# Sheet_1_2021-07-19.net
KiCad netlist of a schematic drawn in Altium Designer
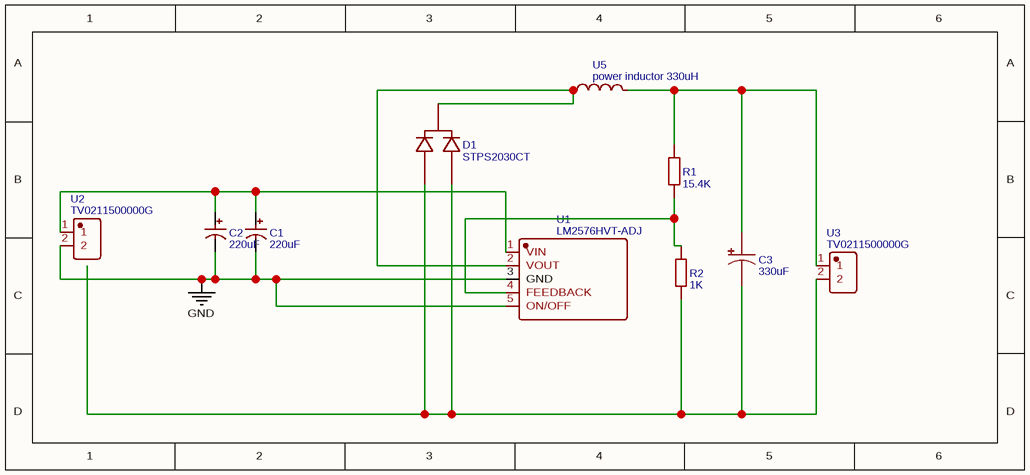
[diagram p0: Sheet_1_2021-07-19.schdoc]

(export (version "E")
  (design (tool "Eeschema 10.0.6"))
  (components
    (comp (ref "C1")
      (value "220uF")
      (fields
        (field (name "BOM_MANUFACTURER PART") "KM221M100I200A")
        (field (name "BOM_SUPPLIER PART") "C59392")
      )
      (libsource (lib "altium-import") (part "root_3_220uF_"))
    )
    (comp (ref "C2")
      (value "220uF")
      (fields
        (field (name "BOM_MANUFACTURER PART") "KM221M100I200A")
        (field (name "BOM_SUPPLIER PART") "C59392")
      )
      (libsource (lib "altium-import") (part "root_3_220uF_"))
    )
    (comp (ref "C3")
      (value "330uF")
      (fields
        (field (name "BOM_SUPPLIER PART") "C116510")
        (field (name "BOM_MANUFACTURER PART") "ERF1KM331L20OT")
        (field (name "CONTRIBUTOR") "LCSC")
      )
      (libsource (lib "altium-import") (part "root_0_330uF_"))
    )
    (comp (ref "D1")
      (value "STPS2030CT")
      (fields (field (name "BOM_SUPPLIER PART") "C171654") (field (name "CONTRIBUTOR") "LCSC"))
      (libsource (lib "altium-import") (part "root_1_STPS2030CT_"))
    )
    (comp (ref "R1")
      (value "15.4K")
      (fields
        (field (name "BOM_SUPPLIER PART") "C246639")
        (field (name "BOM_MANUFACTURER PART") "RTT061542FTP")
        (field (name "CONTRIBUTOR") "LCSC")
      )
      (libsource (lib "altium-import") (part "root_3_15.4K_"))
    )
    (comp (ref "R2")
      (value "1K")
      (fields
        (field (name "BOM_SUPPLIER PART") "C328410")
        (field (name "BOM_MANUFACTURER PART") "AECR1206F1K00K9")
        (field (name "CONTRIBUTOR") "LCSC")
      )
      (libsource (lib "altium-import") (part "root_3_1K_"))
    )
    (comp (ref "U1")
      (value "LM2576HVT-ADJ")
      (fields (field (name "BOM_SUPPLIER PART") "C126041") (field (name "CONTRIBUTOR") "LCSC"))
      (libsource (lib "altium-import") (part "root_0_LM2576HVT-ADJ_"))
    )
    (comp (ref "U2")
      (value "TV0211500000G")
      (fields (field (name "BOM_SUPPLIER PART") "C2683163") (field (name "CONTRIBUTOR") "LCSC"))
      (libsource (lib "altium-import") (part "root_0_TV0211500000G_"))
    )
    (comp (ref "U3")
      (value "TV0211500000G")
      (fields (field (name "BOM_SUPPLIER PART") "C2683163") (field (name "CONTRIBUTOR") "LCSC"))
      (libsource (lib "altium-import") (part "root_0_TV0211500000G_"))
    )
    (comp (ref "U5")
      (value "power inductor 330uH")
      (fields
        (field (name "BOM_MANUFACTURER PART") "74437529203331")
        (field (name "BOM_SUPPLIER PART") "710-74437529203331")
        (field (name "CONTRIBUTOR") "abdin.tesla")
      )
      (libsource (lib "altium-import") (part "root_0_power inductor 330uH_"))
    )
  )
  (nets
    (net (code "1") (name "GND") (class "Default")
      (node (ref "C1") (pin "2") (pinfunction "2_2") (pintype "passive"))
      (node (ref "C2") (pin "2") (pinfunction "2_2") (pintype "passive"))
      (node (ref "U1") (pin "3") (pinfunction "GND_3") (pintype "passive"))
      (node (ref "U1") (pin "5") (pinfunction "ON/OFF_5") (pintype "passive"))
      (node (ref "U2") (pin "2") (pinfunction "2_2") (pintype "passive"))
    )
    (net (code "2") (name "Net-(C3-Pad1)") (class "Default")
      (node (ref "C3") (pin "1") (pinfunction "1_1") (pintype "passive"))
      (node (ref "R1") (pin "1") (pinfunction "1_1") (pintype "passive"))
      (node (ref "U3") (pin "1") (pinfunction "1_1") (pintype "passive"))
      (node (ref "U5") (pin "2") (pinfunction "2_2") (pintype "passive"))
    )
    (net (code "3") (name "Net-(D1-A1)") (class "Default")
      (node (ref "C3") (pin "2") (pinfunction "2_2") (pintype "passive"))
      (node (ref "D1") (pin "1") (pinfunction "A1_1") (pintype "passive"))
      (node (ref "D1") (pin "3") (pinfunction "A2_3") (pintype "passive"))
      (node (ref "R2") (pin "2") (pinfunction "2_2") (pintype "passive"))
      (node (ref "U3") (pin "2") (pinfunction "2_2") (pintype "passive"))
    )
    (net (code "4") (name "Net-(D1-K)") (class "Default")
      (node (ref "D1") (pin "2") (pinfunction "K_2") (pintype "passive"))
      (node (ref "U1") (pin "2") (pinfunction "VOUT_2") (pintype "passive"))
      (node (ref "U5") (pin "1") (pinfunction "1_1") (pintype "passive"))
    )
    (net (code "5") (name "Net-(U1-FEEDBACK)") (class "Default")
      (node (ref "R1") (pin "2") (pinfunction "2_2") (pintype "passive"))
      (node (ref "R2") (pin "1") (pinfunction "1_1") (pintype "passive"))
      (node (ref "U1") (pin "4") (pinfunction "FEEDBACK_4") (pintype "passive"))
    )
    (net (code "6") (name "Net-(U1-VIN)") (class "Default")
      (node (ref "C1") (pin "1") (pinfunction "1_1") (pintype "passive"))
      (node (ref "C2") (pin "1") (pinfunction "1_1") (pintype "passive"))
      (node (ref "U1") (pin "1") (pinfunction "VIN_1") (pintype "passive"))
      (node (ref "U2") (pin "1") (pinfunction "1_1") (pintype "passive"))
    )
  )
)
